# UpperAviPowerSchem.net
KiCad netlist of a schematic drawn in Altium Designer
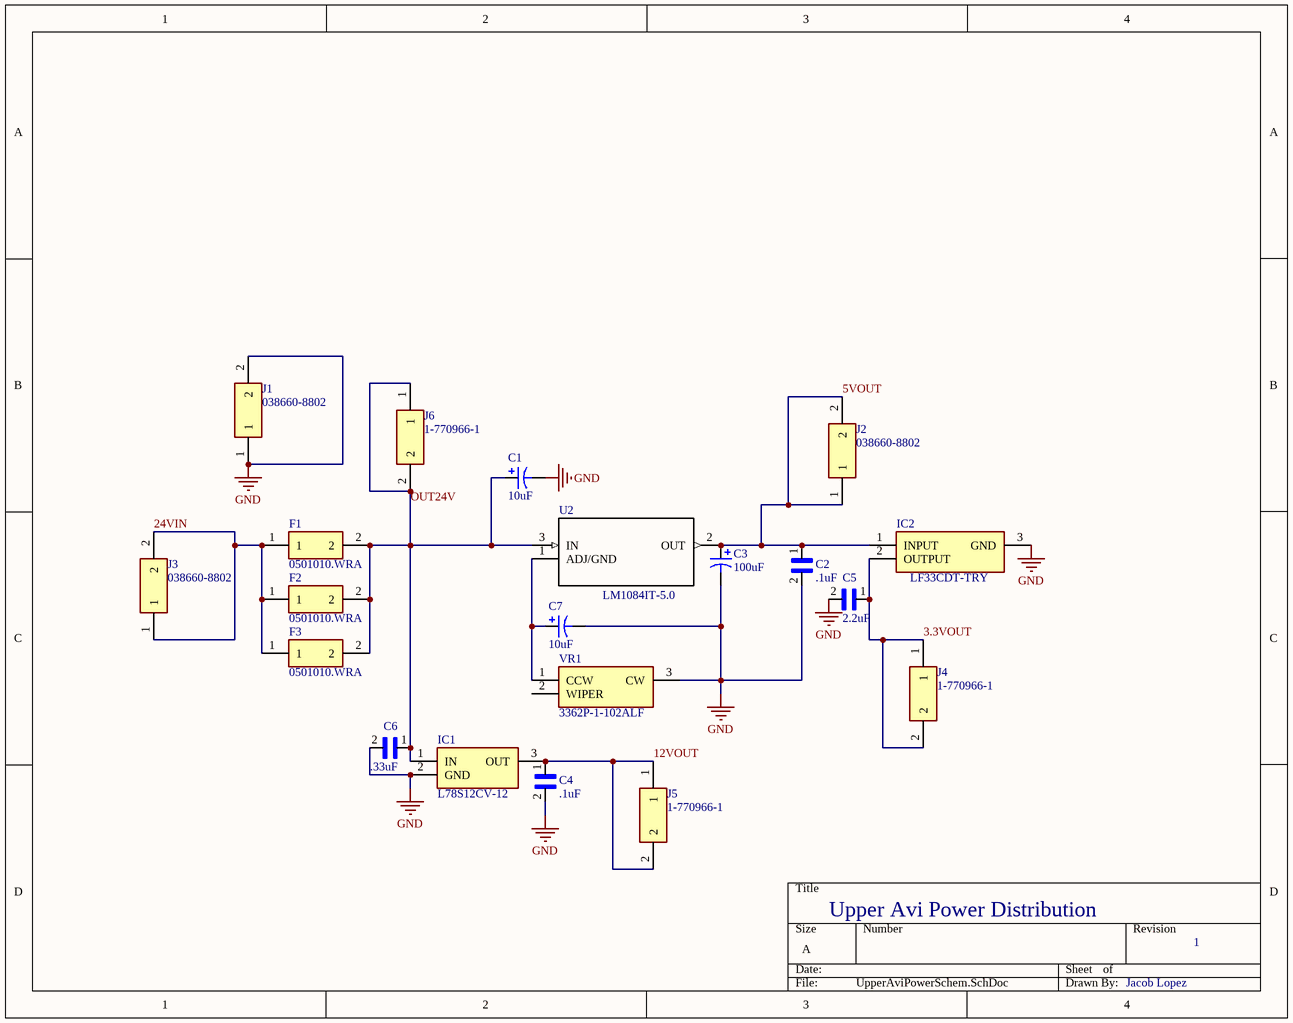
[diagram p0: UpperAviPowerSchem.SchDoc]

(export (version "E")
  (design (tool "Eeschema 10.0.6"))
  (components
    (comp (ref "C1")
      (value "10uF")
      (footprint "CAPR5-4X5")
      (description "Polarized Capacitor (Surface Mount)")
      (fields (field (name "Comment") "Cap Pol3") (field (name "PUBLISHER") "Altium Limited"))
      (libsource (lib "Miscellaneous Devices") (part "Cap Pol3"))
    )
    (comp (ref "C2")
      (value ".1uF")
      (footprint "6-0805_M")
      (description "0603 0.1 uF 50 V Â±10 % Tolerance X7R SMT Multilayer Ceramic Capacitor")
      (fields (field (name "MP") "CC0603KRX7R9BB104") (field (name "MF") "Yageo"))
      (libsource (lib "CC0603KRX7R9BB104") (part "CC0603KRX7R9BB104"))
    )
    (comp (ref "C3")
      (value "100uF")
      (footprint "CAPR5-4X5")
      (description "Polarized Capacitor (Surface Mount)")
      (fields (field (name "Comment") "Cap Pol3") (field (name "PUBLISHER") "Altium Limited"))
      (libsource (lib "Miscellaneous Devices") (part "Cap Pol3"))
    )
    (comp (ref "C4")
      (value ".1uF")
      (footprint "6-0805_M")
      (description "0603 0.1 uF 50 V Â±10 % Tolerance X7R SMT Multilayer Ceramic Capacitor")
      (fields (field (name "MP") "CC0603KRX7R9BB104") (field (name "MF") "Yageo"))
      (libsource (lib "CC0603KRX7R9BB104") (part "CC0603KRX7R9BB104"))
    )
    (comp (ref "C5")
      (value "2.2uF")
      (footprint "6-0805_M")
      (description "0603 0.1 uF 50 V Â±10 % Tolerance X7R SMT Multilayer Ceramic Capacitor")
      (fields (field (name "MP") "CC0603KRX7R9BB104") (field (name "MF") "Yageo"))
      (libsource (lib "CC0603KRX7R9BB104") (part "CC0603KRX7R9BB104"))
    )
    (comp (ref "C6")
      (value ".33uF")
      (footprint "6-0805_M")
      (description "0603 0.1 uF 50 V Â±10 % Tolerance X7R SMT Multilayer Ceramic Capacitor")
      (fields (field (name "MP") "CC0603KRX7R9BB104") (field (name "MF") "Yageo"))
      (libsource (lib "CC0603KRX7R9BB104") (part "CC0603KRX7R9BB104"))
    )
    (comp (ref "C7")
      (value "10uF")
      (footprint "CAPR5-4X5")
      (description "Polarized Capacitor (Surface Mount)")
      (fields (field (name "Comment") "Cap Pol3") (field (name "PUBLISHER") "Altium Limited"))
      (libsource (lib "Miscellaneous Devices") (part "Cap Pol3"))
    )
    (comp (ref "F1")
      (value "0501010.WRA")
      (footprint "SamacSys:FUSC3216X98N")
      (description "Fuse")
      (fields (field (name "MOUSER PART NUMBER") "576-0501010.WRA"))
      (libsource (lib "*") (part "0501010.WRA"))
    )
    (comp (ref "F2")
      (value "0501010.WRA")
      (footprint "SamacSys:FUSC3216X98N")
      (description "Fuse")
      (fields (field (name "MOUSER PART NUMBER") "576-0501010.WRA"))
      (libsource (lib "*") (part "0501010.WRA"))
    )
    (comp (ref "F3")
      (value "0501010.WRA")
      (footprint "SamacSys:FUSC3216X98N")
      (description "Fuse")
      (fields (field (name "MOUSER PART NUMBER") "576-0501010.WRA"))
      (libsource (lib "*") (part "0501010.WRA"))
    )
    (comp (ref "IC1")
      (value "L78S12CV-12")
      (footprint "SamacSys:TO270P460X1020X2008-3P")
      (description "Integrated Circuit")
      (fields
        (field (name "MOUSER PART NUMBER") "511-L78S12CV")
        (field (name "MANUFACTURER_PART_NUMBER") "L78S12CV")
      )
      (libsource (lib "*") (part "L78S12CV"))
    )
    (comp (ref "IC2")
      (value "LF33CDT-TRY")
      (footprint "SamacSys:LD1117DT33")
      (description "Integrated Circuit")
      (fields (field (name "MOUSER PART NUMBER") "511-LF33CDT-TRY"))
      (libsource (lib "*") (part "LF33CDT-TRY"))
    )
    (comp (ref "J1")
      (value "038660-8802")
      (footprint "SamacSys:0386608802")
      (description "Connector")
      (libsource (lib "*") (part "038660-8802"))
    )
    (comp (ref "J2")
      (value "038660-8802")
      (footprint "SamacSys:0386608802")
      (description "Connector")
      (libsource (lib "*") (part "038660-8802"))
    )
    (comp (ref "J3")
      (value "038660-8802")
      (footprint "SamacSys:0386608802")
      (description "Connector")
      (libsource (lib "*") (part "038660-8802"))
    )
    (comp (ref "J4")
      (value "1-770966-1")
      (footprint "SamacSys:17709661")
      (description "Connector")
      (fields (field (name "MOUSER PART NUMBER") "571-1-770966-1") (field (name "RS PART NUMBER") "7099906"))
      (libsource (lib "*") (part "1-770966-1"))
    )
    (comp (ref "J5")
      (value "1-770966-1")
      (footprint "SamacSys:17709661")
      (description "Connector")
      (fields (field (name "MOUSER PART NUMBER") "571-1-770966-1") (field (name "RS PART NUMBER") "7099906"))
      (libsource (lib "*") (part "1-770966-1"))
    )
    (comp (ref "J6")
      (value "1-770966-1")
      (footprint "SamacSys:17709661")
      (description "Connector")
      (fields (field (name "MOUSER PART NUMBER") "571-1-770966-1") (field (name "RS PART NUMBER") "7099906"))
      (libsource (lib "*") (part "1-770966-1"))
    )
    (comp (ref "U2")
      (value "LM1084IT-5.0")
      (footprint "*TO254P470X1016X2222-3P")
      (description "Voltage stabiliser; LDO, fixed; 5V; 5A; TO220; THT; 1.2")
      (fields (field (name "MF") "Texas Instruments") (field (name "MP") "LM1084IT-5.0/NOPB"))
      (libsource (lib "LM1084IT-5.0") (part "LM1084IT-5.0"))
    )
    (comp (ref "VR1")
      (value "3362P-1-102ALF")
      (footprint "SamacSys:3362P_1")
      (description "Variable Resistor")
      (fields (field (name "MOUSER PART NUMBER") "652-3362P-1-102ALF"))
      (libsource (lib "*") (part "3362P-1-102ALF"))
    )
  )
  (nets
    (net (code "1") (name "/3.3VOUT") (class "Default")
      (node (ref "C5") (pin "1") (pinfunction "1_1") (pintype "passive"))
      (node (ref "IC2") (pin "2") (pinfunction "OUTPUT_2") (pintype "passive"))
      (node (ref "J4") (pin "1") (pinfunction "1_1") (pintype "passive"))
      (node (ref "J4") (pin "2") (pinfunction "2_2") (pintype "passive"))
    )
    (net (code "2") (name "/5VOUT") (class "Default")
      (node (ref "C2") (pin "1") (pinfunction "1_1") (pintype "passive"))
      (node (ref "C3") (pin "1") (pinfunction "1_1") (pintype "passive"))
      (node (ref "IC2") (pin "1") (pinfunction "INPUT_1") (pintype "passive"))
      (node (ref "J2") (pin "1") (pinfunction "1_1") (pintype "passive"))
      (node (ref "J2") (pin "2") (pinfunction "2_2") (pintype "passive"))
      (node (ref "U2") (pin "2") (pinfunction "OUT_2") (pintype "output"))
    )
    (net (code "3") (name "/12VOUT") (class "Default")
      (node (ref "C4") (pin "1") (pinfunction "1_1") (pintype "passive"))
      (node (ref "IC1") (pin "3") (pinfunction "OUT_3") (pintype "power_in"))
      (node (ref "J5") (pin "1") (pinfunction "1_1") (pintype "passive"))
      (node (ref "J5") (pin "2") (pinfunction "2_2") (pintype "passive"))
    )
    (net (code "4") (name "/24VIN") (class "Default")
      (node (ref "F1") (pin "1") (pinfunction "1_1") (pintype "passive"))
      (node (ref "F2") (pin "1") (pinfunction "1_1") (pintype "passive"))
      (node (ref "F3") (pin "1") (pinfunction "1_1") (pintype "passive"))
      (node (ref "J3") (pin "1") (pinfunction "1_1") (pintype "passive"))
      (node (ref "J3") (pin "2") (pinfunction "2_2") (pintype "passive"))
    )
    (net (code "5") (name "/OUT24V") (class "Default")
      (node (ref "C1") (pin "1") (pinfunction "1_1") (pintype "passive"))
      (node (ref "C6") (pin "1") (pinfunction "1_1") (pintype "passive"))
      (node (ref "F1") (pin "2") (pinfunction "2_2") (pintype "passive"))
      (node (ref "F2") (pin "2") (pinfunction "2_2") (pintype "passive"))
      (node (ref "F3") (pin "2") (pinfunction "2_2") (pintype "passive"))
      (node (ref "IC1") (pin "1") (pinfunction "IN_1") (pintype "power_in"))
      (node (ref "J6") (pin "1") (pinfunction "1_1") (pintype "passive"))
      (node (ref "J6") (pin "2") (pinfunction "2_2") (pintype "passive"))
      (node (ref "U2") (pin "3") (pinfunction "IN_3") (pintype "input"))
    )
    (net (code "6") (name "GND") (class "Default")
      (node (ref "C1") (pin "2") (pinfunction "2_2") (pintype "passive"))
      (node (ref "C2") (pin "2") (pinfunction "2_2") (pintype "passive"))
      (node (ref "C3") (pin "2") (pinfunction "2_2") (pintype "passive"))
      (node (ref "C4") (pin "2") (pinfunction "2_2") (pintype "passive"))
      (node (ref "C5") (pin "2") (pinfunction "2_2") (pintype "passive"))
      (node (ref "C6") (pin "2") (pinfunction "2_2") (pintype "passive"))
      (node (ref "C7") (pin "2") (pinfunction "2_2") (pintype "passive"))
      (node (ref "IC1") (pin "2") (pinfunction "GND_2") (pintype "power_in"))
      (node (ref "IC2") (pin "3") (pinfunction "GND_3") (pintype "passive"))
      (node (ref "J1") (pin "1") (pinfunction "1_1") (pintype "passive"))
      (node (ref "J1") (pin "2") (pinfunction "2_2") (pintype "passive"))
      (node (ref "VR1") (pin "3") (pinfunction "CW_3") (pintype "passive"))
    )
    (net (code "7") (name "Net-(U2-ADJ{slash}GND)") (class "Default")
      (node (ref "C7") (pin "1") (pinfunction "1_1") (pintype "passive"))
      (node (ref "U2") (pin "1") (pinfunction "ADJ/GND_1") (pintype "passive"))
      (node (ref "VR1") (pin "1") (pinfunction "CCW_1") (pintype "passive"))
    )
    (net (code "8") (name "unconnected-(VR1-WIPER-Pad2)") (class "Default")
      (node (ref "VR1") (pin "2") (pinfunction "WIPER_2") (pintype "passive"))
    )
  )
)
